# MINI_SAM_D51_r002_b002.net
KiCad netlist of a schematic drawn in EAGLE
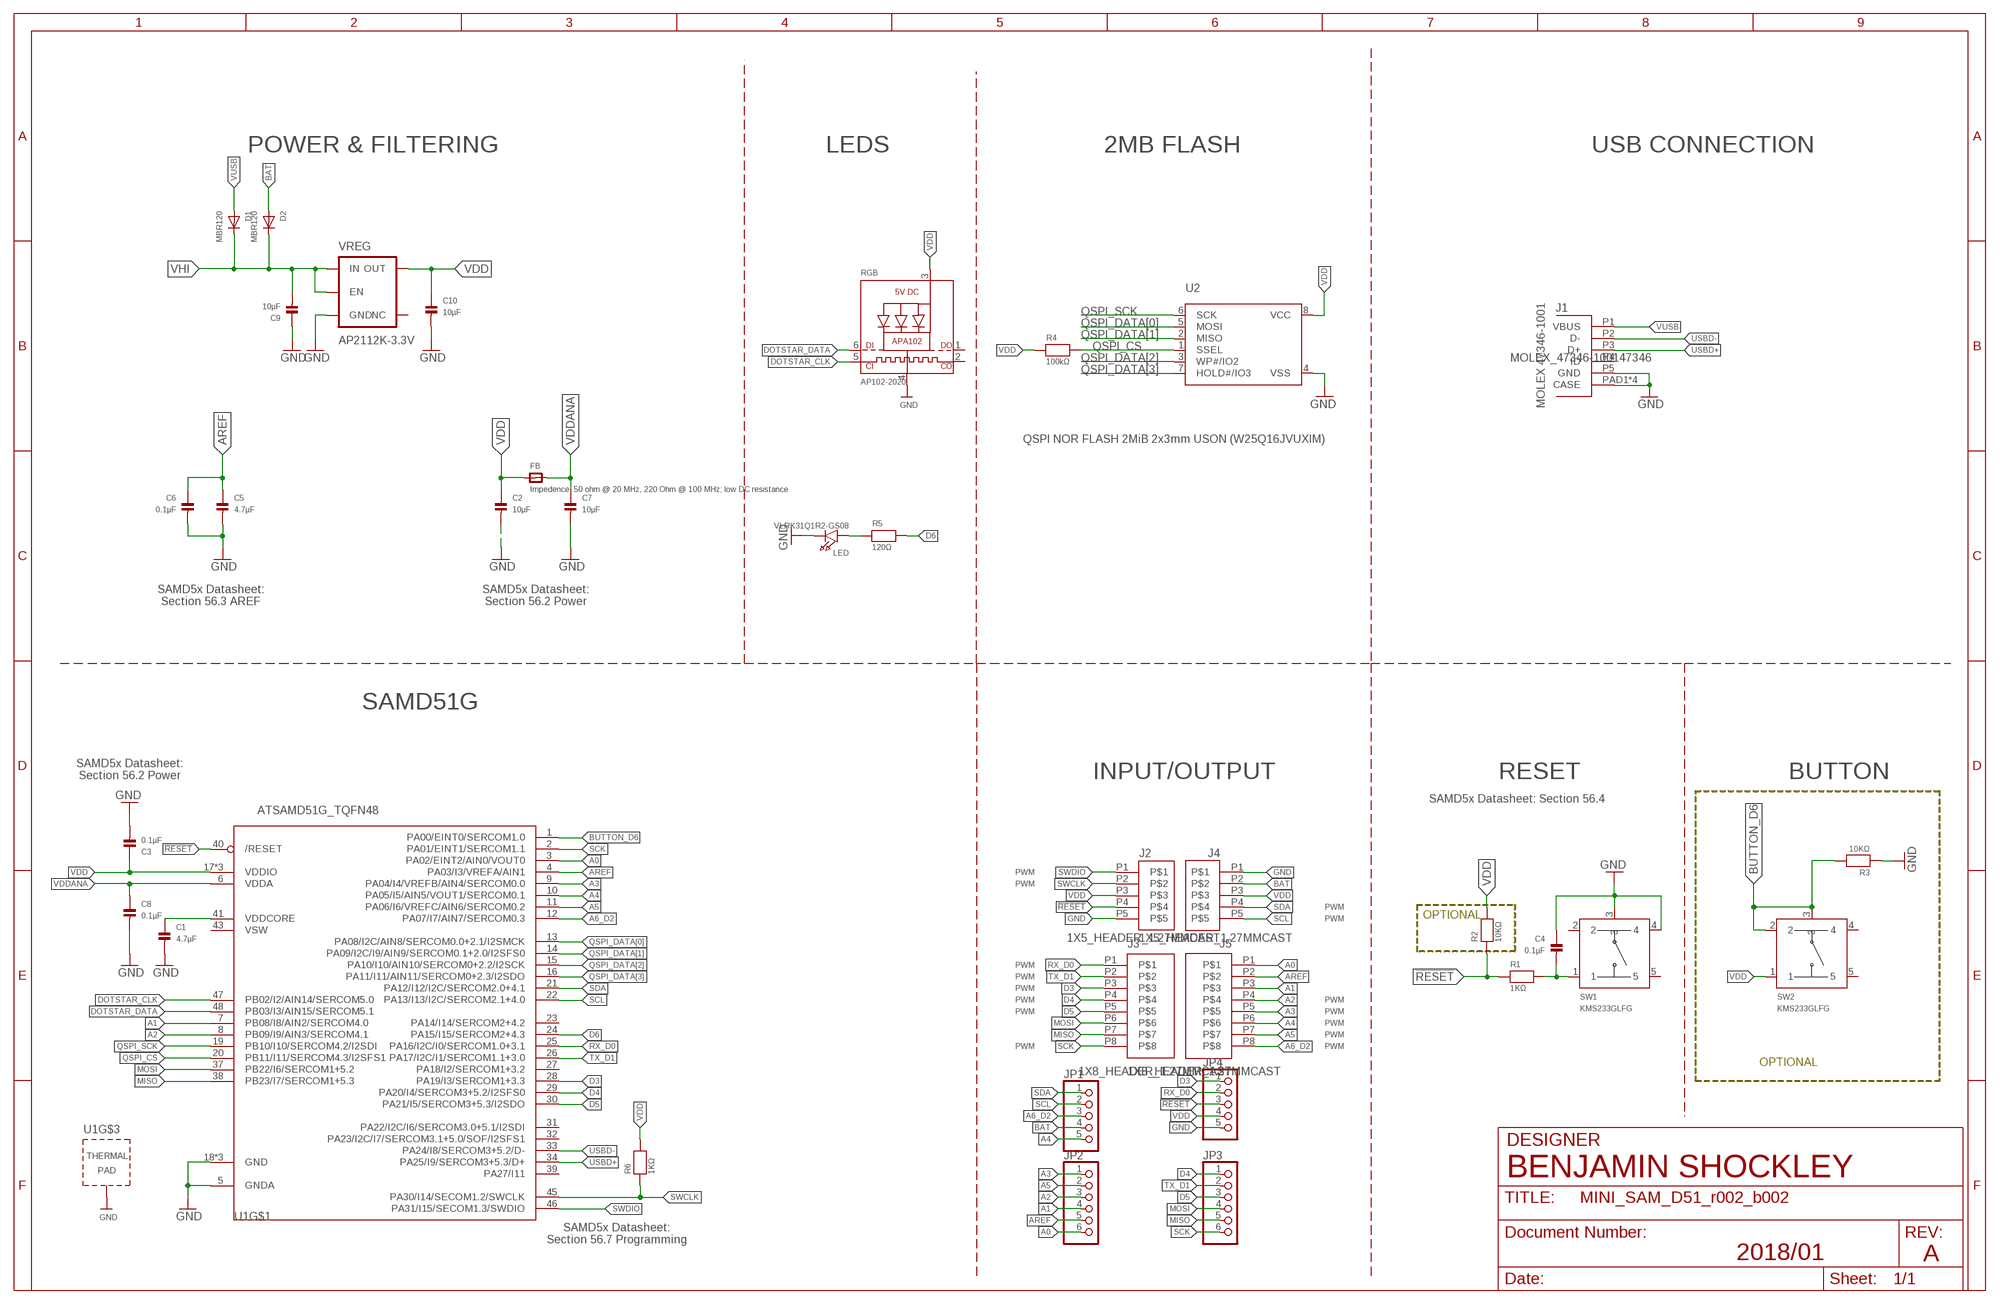
[diagram p0: schematic, sheet 1]

(export (version "E")
  (design (tool "Eeschema 10.0.6"))
  (components
    (comp (ref "C1")
      (value "4.7µF")
      (footprint "eagle-import:_0603MP")
      (libsource (lib "eagle-import") (part "CAP_CERAMIC_0603MP"))
    )
    (comp (ref "C2")
      (value "10µF")
      (footprint "eagle-import:_0603MP")
      (libsource (lib "eagle-import") (part "CAP_CERAMIC_0603MP"))
    )
    (comp (ref "C3")
      (value "0.1µF")
      (footprint "eagle-import:_0603MP")
      (libsource (lib "eagle-import") (part "CAP_CERAMIC_0603MP"))
    )
    (comp (ref "C4")
      (value "0.1µF")
      (footprint "eagle-import:_0603MP")
      (libsource (lib "eagle-import") (part "CAP_CERAMIC_0603MP"))
    )
    (comp (ref "C5")
      (value "4.7µF")
      (footprint "eagle-import:_0603MP")
      (libsource (lib "eagle-import") (part "CAP_CERAMIC_0603MP"))
    )
    (comp (ref "C6")
      (value "0.1µF")
      (footprint "eagle-import:_0603MP")
      (libsource (lib "eagle-import") (part "CAP_CERAMIC_0603MP"))
    )
    (comp (ref "C7")
      (value "10µF")
      (footprint "eagle-import:_0603MP")
      (libsource (lib "eagle-import") (part "CAP_CERAMIC_0603MP"))
    )
    (comp (ref "C8")
      (value "0.1µF")
      (footprint "eagle-import:_0603MP")
      (libsource (lib "eagle-import") (part "CAP_CERAMIC_0603MP"))
    )
    (comp (ref "C9")
      (value "10µF")
      (footprint "eagle-import:_0603MP")
      (libsource (lib "eagle-import") (part "CAP_CERAMIC_0603MP"))
    )
    (comp (ref "C10")
      (value "10µF")
      (footprint "eagle-import:_0603MP")
      (libsource (lib "eagle-import") (part "CAP_CERAMIC_0603MP"))
    )
    (comp (ref "D1")
      (value "MBR120")
      (footprint "eagle-import:SOD-123FL")
      (libsource (lib "eagle-import") (part "DIODE_SOD-123FL"))
    )
    (comp (ref "D2")
      (value "MBR120")
      (footprint "eagle-import:SOD-123FL")
      (libsource (lib "eagle-import") (part "DIODE_SOD-123FL"))
    )
    (comp (ref "FB")
      (value "Impedence: 50 ohm @ 20 MHz, 220 Ohm @ 100 MHz; low DC resistance")
      (footprint "eagle-import:_0603MP")
      (libsource (lib "eagle-import") (part "FERRITE_0603MP"))
    )
    (comp (ref "J1")
      (value "MOLEX_47346-100147346")
      (footprint "eagle-import:MOLEX_47346-1001")
      (libsource (lib "eagle-import") (part "MOLEX_47346-100147346"))
    )
    (comp (ref "J2")
      (value "1X5_HEADER_1.27MMCAST")
      (footprint "eagle-import:1X5_HEADER_1.27MM_CASTELLATED")
      (libsource (lib "eagle-import") (part "1X5_HEADER_1.27MMCAST"))
    )
    (comp (ref "J3")
      (value "1X8_HEADER_1.27MMCAST")
      (footprint "eagle-import:1X8_HEADER_1.27MM_CASTELLATED")
      (libsource (lib "eagle-import") (part "1X8_HEADER_1.27MMCAST"))
    )
    (comp (ref "J4")
      (value "1X5_HEADER_1.27MMCAST")
      (footprint "eagle-import:1X5_HEADER_1.27MM_CASTELLATED")
      (libsource (lib "eagle-import") (part "1X5_HEADER_1.27MMCAST"))
    )
    (comp (ref "J5")
      (value "1X8_HEADER_1.27MMCAST")
      (footprint "eagle-import:1X8_HEADER_1.27MM_CASTELLATED")
      (libsource (lib "eagle-import") (part "1X8_HEADER_1.27MMCAST"))
    )
    (comp (ref "JP1")
      (value "PINHD-1X51X05_SMT")
      (footprint "eagle-import:1X05_SMT")
      (libsource (lib "eagle-import") (part "PINHD-1X51X05_SMT"))
    )
    (comp (ref "JP2")
      (value "PINHD-1X61X06_SMT")
      (footprint "eagle-import:1X06_SMT")
      (libsource (lib "eagle-import") (part "PINHD-1X61X06_SMT"))
    )
    (comp (ref "JP3")
      (value "PINHD-1X6REV")
      (footprint "eagle-import:1X06_SMT_REV")
      (libsource (lib "eagle-import") (part "PINHD-1X6REV"))
    )
    (comp (ref "JP4")
      (value "PINHD-1X51X05_SMT")
      (footprint "eagle-import:1X05_SMT")
      (libsource (lib "eagle-import") (part "PINHD-1X51X05_SMT"))
    )
    (comp (ref "LED")
      (value "VLRK31Q1R2-GS08")
      (footprint "eagle-import:REVERSE_MOUNT_LED")
      (libsource (lib "eagle-import") (part "REVERSEMOUNTLED"))
    )
    (comp (ref "R1")
      (value "1KΩ")
      (footprint "eagle-import:_0603MP")
      (libsource (lib "eagle-import") (part "RESISTOR_0603MP"))
    )
    (comp (ref "R2")
      (value "10KΩ")
      (footprint "eagle-import:_0603MP")
      (libsource (lib "eagle-import") (part "RESISTOR_0603MP"))
    )
    (comp (ref "R3")
      (value "10KΩ")
      (footprint "eagle-import:_0603MP")
      (libsource (lib "eagle-import") (part "RESISTOR_0603MP"))
    )
    (comp (ref "R4")
      (value "100kΩ")
      (footprint "eagle-import:_0603MP")
      (libsource (lib "eagle-import") (part "RESISTOR_0603MP"))
    )
    (comp (ref "R5")
      (value "120Ω")
      (footprint "eagle-import:_0603MP")
      (libsource (lib "eagle-import") (part "RESISTOR_0603MP"))
    )
    (comp (ref "R6")
      (value "1KΩ")
      (footprint "eagle-import:_0603MP")
      (libsource (lib "eagle-import") (part "RESISTOR_0603MP"))
    )
    (comp (ref "RGB")
      (value "AP102-2020")
      (footprint "eagle-import:APA102_2020")
      (libsource (lib "eagle-import") (part "APA1022020"))
    )
    (comp (ref "SW1")
      (value "KMS233GLFG")
      (footprint "eagle-import:KMS_SWITCH")
      (libsource (lib "eagle-import") (part "KMS_SWITCHKMS"))
    )
    (comp (ref "SW2")
      (value "KMS233GLFG")
      (footprint "eagle-import:KMS_SWITCH")
      (libsource (lib "eagle-import") (part "KMS_SWITCHKMS"))
    )
    (comp (ref "U1")
      (value "ATSAMD51G_TQFN48")
      (footprint "eagle-import:TQFN48_7MM")
      (libsource (lib "eagle-import") (part "ATSAMD51G_TQFN48"))
    )
    (comp (ref "U2")
      (value "QSPI NOR FLASH 2MiB 2x3mm USON (W25Q16JVUXIM)")
      (footprint "eagle-import:USON8")
      (libsource (lib "eagle-import") (part "SPIFLASH_8PINUX"))
    )
    (comp (ref "VREG")
      (value "AP2112K-3.3V")
      (footprint "eagle-import:SOT23-5")
      (libsource (lib "eagle-import") (part "V_REG_AP2112K-3.3V"))
    )
  )
  (nets
    (net (code "1") (name "/VSW") (class "Default")
      (node (ref "U1") (pin "43") (pinfunction "VSW_43") (pintype "power_in"))
    )
    (net (code "2") (name "/~{RESET}") (class "Default")
      (node (ref "J2") (pin "P4") (pinfunction "P$4_P4") (pintype "bidirectional"))
      (node (ref "JP4") (pin "3") (pinfunction "3_3") (pintype "passive"))
      (node (ref "R1") (pin "1") (pinfunction "1_1") (pintype "passive"))
      (node (ref "R2") (pin "1") (pinfunction "1_1") (pintype "passive"))
      (node (ref "U1") (pin "40") (pinfunction "/RESET_40") (pintype "bidirectional"))
    )
    (net (code "3") (name "A0") (class "Default")
      (node (ref "J5") (pin "P1") (pinfunction "P$1_P1") (pintype "bidirectional"))
      (node (ref "JP2") (pin "6") (pinfunction "6_6") (pintype "passive"))
      (node (ref "U1") (pin "3") (pinfunction "PA02/EINT2/AIN0/VOUT0_3") (pintype "bidirectional"))
    )
    (net (code "4") (name "A1") (class "Default")
      (node (ref "J5") (pin "P3") (pinfunction "P$3_P3") (pintype "bidirectional"))
      (node (ref "JP2") (pin "4") (pinfunction "4_4") (pintype "passive"))
      (node (ref "U1") (pin "7") (pinfunction "PB08/I8/AIN2/SERCOM4.0_7") (pintype "bidirectional"))
    )
    (net (code "5") (name "A2") (class "Default")
      (node (ref "J5") (pin "P4") (pinfunction "P$4_P4") (pintype "bidirectional"))
      (node (ref "JP2") (pin "3") (pinfunction "3_3") (pintype "passive"))
      (node (ref "U1") (pin "8") (pinfunction "PB09/I9/AIN3/SERCOM4.1_8") (pintype "bidirectional"))
    )
    (net (code "6") (name "A3") (class "Default")
      (node (ref "J5") (pin "P5") (pinfunction "P$5_P5") (pintype "bidirectional"))
      (node (ref "JP2") (pin "1") (pinfunction "1_1") (pintype "passive"))
      (node (ref "U1") (pin "9") (pinfunction "PA04/I4/VREFB/AIN4/SERCOM0.0_9") (pintype "bidirectional"))
    )
    (net (code "7") (name "A4") (class "Default")
      (node (ref "J5") (pin "P6") (pinfunction "P$6_P6") (pintype "bidirectional"))
      (node (ref "JP1") (pin "5") (pinfunction "5_5") (pintype "passive"))
      (node (ref "U1") (pin "10") (pinfunction "PA05/I5/AIN5/VOUT1/SERCOM0.1_10") (pintype "bidirectional"))
    )
    (net (code "8") (name "A5") (class "Default")
      (node (ref "J5") (pin "P7") (pinfunction "P$7_P7") (pintype "bidirectional"))
      (node (ref "JP2") (pin "2") (pinfunction "2_2") (pintype "passive"))
      (node (ref "U1") (pin "11") (pinfunction "PA06/I6/VREFC/AIN6/SERCOM0.2_11") (pintype "bidirectional"))
    )
    (net (code "9") (name "A6_D2") (class "Default")
      (node (ref "J5") (pin "P8") (pinfunction "P$8_P8") (pintype "bidirectional"))
      (node (ref "JP1") (pin "3") (pinfunction "3_3") (pintype "passive"))
      (node (ref "U1") (pin "12") (pinfunction "PA07/I7/AIN7/SERCOM0.3_12") (pintype "bidirectional"))
    )
    (net (code "10") (name "AREF") (class "Default")
      (node (ref "C5") (pin "1") (pinfunction "P$1_1") (pintype "passive"))
      (node (ref "C6") (pin "1") (pinfunction "P$1_1") (pintype "passive"))
      (node (ref "J5") (pin "P2") (pinfunction "P$2_P2") (pintype "bidirectional"))
      (node (ref "JP2") (pin "5") (pinfunction "5_5") (pintype "passive"))
      (node (ref "U1") (pin "4") (pinfunction "PA03/I3/VREFA/AIN1_4") (pintype "bidirectional"))
    )
    (net (code "11") (name "BAT") (class "Default")
      (node (ref "D2") (pin "A") (pinfunction "A_A") (pintype "passive"))
      (node (ref "J4") (pin "P2") (pinfunction "P$2_P2") (pintype "bidirectional"))
      (node (ref "JP1") (pin "4") (pinfunction "4_4") (pintype "passive"))
    )
    (net (code "12") (name "BUTTON_D6") (class "Default")
      (node (ref "R3") (pin "2") (pinfunction "2_2") (pintype "passive"))
      (node (ref "SW2") (pin "2") (pinfunction "2_2") (pintype "bidirectional"))
      (node (ref "SW2") (pin "3") (pinfunction "3_3") (pintype "bidirectional"))
      (node (ref "U1") (pin "1") (pinfunction "PA00/EINT0/SERCOM1.0_1") (pintype "bidirectional"))
    )
    (net (code "13") (name "D3") (class "Default")
      (node (ref "J3") (pin "P3") (pinfunction "P$3_P3") (pintype "bidirectional"))
      (node (ref "JP4") (pin "1") (pinfunction "1_1") (pintype "passive"))
      (node (ref "U1") (pin "28") (pinfunction "PA19/I3/SERCOM1+3.3_28") (pintype "bidirectional"))
    )
    (net (code "14") (name "D4") (class "Default")
      (node (ref "J3") (pin "P4") (pinfunction "P$4_P4") (pintype "bidirectional"))
      (node (ref "JP3") (pin "1") (pinfunction "1_1") (pintype "passive"))
      (node (ref "U1") (pin "29") (pinfunction "PA20/I4/SERCOM3+5.2/I2SFS0_29") (pintype "bidirectional"))
    )
    (net (code "15") (name "D5") (class "Default")
      (node (ref "J3") (pin "P5") (pinfunction "P$5_P5") (pintype "bidirectional"))
      (node (ref "JP3") (pin "3") (pinfunction "3_3") (pintype "passive"))
      (node (ref "U1") (pin "30") (pinfunction "PA21/I5/SERCOM3+5.3/I2SDO_30") (pintype "bidirectional"))
    )
    (net (code "16") (name "D6") (class "Default")
      (node (ref "R5") (pin "2") (pinfunction "2_2") (pintype "passive"))
      (node (ref "U1") (pin "24") (pinfunction "PA15/I15/SERCOM2+4.3_24") (pintype "bidirectional"))
    )
    (net (code "17") (name "DOTSTAR_CLK") (class "Default")
      (node (ref "RGB") (pin "5") (pinfunction "CKI_5") (pintype "input"))
      (node (ref "U1") (pin "47") (pinfunction "PB02/I2/AIN14/SERCOM5.0_47") (pintype "bidirectional"))
    )
    (net (code "18") (name "DOTSTAR_DATA") (class "Default")
      (node (ref "RGB") (pin "6") (pinfunction "DI_6") (pintype "input"))
      (node (ref "U1") (pin "48") (pinfunction "PB03/I3/AIN15/SERCOM5.1_48") (pintype "bidirectional"))
    )
    (net (code "19") (name "GND") (class "Default")
      (node (ref "C1") (pin "2") (pinfunction "P$2_2") (pintype "passive"))
      (node (ref "C10") (pin "2") (pinfunction "P$2_2") (pintype "passive"))
      (node (ref "C2") (pin "2") (pinfunction "P$2_2") (pintype "passive"))
      (node (ref "C3") (pin "2") (pinfunction "P$2_2") (pintype "passive"))
      (node (ref "C4") (pin "1") (pinfunction "P$1_1") (pintype "passive"))
      (node (ref "C5") (pin "2") (pinfunction "P$2_2") (pintype "passive"))
      (node (ref "C6") (pin "2") (pinfunction "P$2_2") (pintype "passive"))
      (node (ref "C7") (pin "2") (pinfunction "P$2_2") (pintype "passive"))
      (node (ref "C8") (pin "2") (pinfunction "P$2_2") (pintype "passive"))
      (node (ref "C9") (pin "1") (pinfunction "P$1_1") (pintype "passive"))
      (node (ref "J1") (pin "P5") (pinfunction "GND_P5") (pintype "power_in"))
      (node (ref "J1") (pin "PAD1") (pinfunction "CASE_PAD1") (pintype "bidirectional"))
      (node (ref "J1") (pin "PAD2") (pinfunction "CASE_PAD2") (pintype "bidirectional"))
      (node (ref "J1") (pin "PAD3") (pinfunction "CASE_PAD3") (pintype "bidirectional"))
      (node (ref "J1") (pin "PAD4") (pinfunction "CASE_PAD4") (pintype "bidirectional"))
      (node (ref "J2") (pin "P5") (pinfunction "P$5_P5") (pintype "bidirectional"))
      (node (ref "J4") (pin "P1") (pinfunction "P$1_P1") (pintype "bidirectional"))
      (node (ref "JP4") (pin "5") (pinfunction "5_5") (pintype "passive"))
      (node (ref "LED") (pin "C") (pinfunction "C_C") (pintype "passive"))
      (node (ref "R3") (pin "1") (pinfunction "1_1") (pintype "passive"))
      (node (ref "RGB") (pin "4") (pinfunction "GND_4") (pintype "power_in"))
      (node (ref "SW1") (pin "3") (pinfunction "3_3") (pintype "bidirectional"))
      (node (ref "SW1") (pin "4") (pinfunction "4_4") (pintype "bidirectional"))
      (node (ref "U1") (pin "18") (pinfunction "GND_18") (pintype "power_in"))
      (node (ref "U1") (pin "35") (pinfunction "GND_35") (pintype "power_in"))
      (node (ref "U1") (pin "42") (pinfunction "GND_42") (pintype "power_in"))
      (node (ref "U1") (pin "5") (pinfunction "GNDA_5") (pintype "power_in"))
      (node (ref "U1") (pin "THERMAL") (pinfunction "TP_THERMAL") (pintype "power_in"))
      (node (ref "U2") (pin "4") (pinfunction "VSS_4") (pintype "bidirectional"))
      (node (ref "VREG") (pin "2") (pinfunction "GND_2") (pintype "input"))
    )
    (net (code "20") (name "MISO") (class "Default")
      (node (ref "J3") (pin "P7") (pinfunction "P$7_P7") (pintype "bidirectional"))
      (node (ref "JP3") (pin "5") (pinfunction "5_5") (pintype "passive"))
      (node (ref "U1") (pin "38") (pinfunction "PB23/I7/SERCOM1+5.3_38") (pintype "bidirectional"))
    )
    (net (code "21") (name "MOSI") (class "Default")
      (node (ref "J3") (pin "P6") (pinfunction "P$6_P6") (pintype "bidirectional"))
      (node (ref "JP3") (pin "4") (pinfunction "4_4") (pintype "passive"))
      (node (ref "U1") (pin "37") (pinfunction "PB22/I6/SERCOM1+5.2_37") (pintype "bidirectional"))
    )
    (net (code "22") (name "Net-(C1-P$1)") (class "Default")
      (node (ref "C1") (pin "1") (pinfunction "P$1_1") (pintype "passive"))
      (node (ref "U1") (pin "41") (pinfunction "VDDCORE_41") (pintype "power_in"))
    )
    (net (code "23") (name "Net-(C4-P$2)") (class "Default")
      (node (ref "C4") (pin "2") (pinfunction "P$2_2") (pintype "passive"))
      (node (ref "R1") (pin "2") (pinfunction "2_2") (pintype "passive"))
      (node (ref "SW1") (pin "1") (pinfunction "1_1") (pintype "bidirectional"))
    )
    (net (code "24") (name "Net-(LED-PadA)") (class "Default")
      (node (ref "LED") (pin "A") (pinfunction "A_A") (pintype "passive"))
      (node (ref "R5") (pin "1") (pinfunction "1_1") (pintype "passive"))
    )
    (net (code "25") (name "QSPI_CS") (class "Default")
      (node (ref "R4") (pin "2") (pinfunction "2_2") (pintype "passive"))
      (node (ref "U1") (pin "20") (pinfunction "PB11/I11/SERCOM4.3/I2SFS1_20") (pintype "bidirectional"))
      (node (ref "U2") (pin "1") (pinfunction "SSEL_1") (pintype "bidirectional"))
    )
    (net (code "26") (name "QSPI_DATA[0]") (class "Default")
      (node (ref "U1") (pin "13") (pinfunction "PA08/I2C/AIN8/SERCOM0.0+2.1/I2SMCK_13") (pintype "bidirectional"))
      (node (ref "U2") (pin "5") (pinfunction "MOSI_5") (pintype "bidirectional"))
    )
    (net (code "27") (name "QSPI_DATA[1]") (class "Default")
      (node (ref "U1") (pin "14") (pinfunction "PA09/I2C/I9/AIN9/SERCOM0.1+2.0/I2SFS0_14") (pintype "bidirectional"))
      (node (ref "U2") (pin "2") (pinfunction "MISO_2") (pintype "bidirectional"))
    )
    (net (code "28") (name "QSPI_DATA[2]") (class "Default")
      (node (ref "U1") (pin "15") (pinfunction "PA10/I10/AIN10/SERCOM0+2.2/I2SCK_15") (pintype "bidirectional"))
      (node (ref "U2") (pin "3") (pinfunction "WP#/IO2_3") (pintype "bidirectional"))
    )
    (net (code "29") (name "QSPI_DATA[3]") (class "Default")
      (node (ref "U1") (pin "16") (pinfunction "PA11/I11/AIN11/SERCOM0+2.3/I2SDO_16") (pintype "bidirectional"))
      (node (ref "U2") (pin "7") (pinfunction "HOLD#/IO3_7") (pintype "bidirectional"))
    )
    (net (code "30") (name "QSPI_SCK") (class "Default")
      (node (ref "U1") (pin "19") (pinfunction "PB10/I10/SERCOM4.2/I2SDI_19") (pintype "bidirectional"))
      (node (ref "U2") (pin "6") (pinfunction "SCK_6") (pintype "bidirectional"))
    )
    (net (code "31") (name "RX_D0") (class "Default")
      (node (ref "J3") (pin "P1") (pinfunction "P$1_P1") (pintype "bidirectional"))
      (node (ref "JP4") (pin "2") (pinfunction "2_2") (pintype "passive"))
      (node (ref "U1") (pin "25") (pinfunction "PA16/I2C/I0/SERCOM1.0+3.1_25") (pintype "bidirectional"))
    )
    (net (code "32") (name "SCK") (class "Default")
      (node (ref "J3") (pin "P8") (pinfunction "P$8_P8") (pintype "bidirectional"))
      (node (ref "JP3") (pin "6") (pinfunction "6_6") (pintype "passive"))
      (node (ref "U1") (pin "2") (pinfunction "PA01/EINT1/SERCOM1.1_2") (pintype "bidirectional"))
    )
    (net (code "33") (name "SCL") (class "Default")
      (node (ref "J4") (pin "P5") (pinfunction "P$5_P5") (pintype "bidirectional"))
      (node (ref "JP1") (pin "2") (pinfunction "2_2") (pintype "passive"))
      (node (ref "U1") (pin "22") (pinfunction "PA13/I13/I2C/SERCOM2.1+4.0_22") (pintype "bidirectional"))
    )
    (net (code "34") (name "SDA") (class "Default")
      (node (ref "J4") (pin "P4") (pinfunction "P$4_P4") (pintype "bidirectional"))
      (node (ref "JP1") (pin "1") (pinfunction "1_1") (pintype "passive"))
      (node (ref "U1") (pin "21") (pinfunction "PA12/I12/I2C/SERCOM2.0+4.1_21") (pintype "bidirectional"))
    )
    (net (code "35") (name "SWCLK") (class "Default")
      (node (ref "J2") (pin "P2") (pinfunction "P$2_P2") (pintype "bidirectional"))
      (node (ref "R6") (pin "1") (pinfunction "1_1") (pintype "passive"))
      (node (ref "U1") (pin "45") (pinfunction "PA30/I14/SECOM1.2/SWCLK_45") (pintype "bidirectional"))
    )
    (net (code "36") (name "SWDIO") (class "Default")
      (node (ref "J2") (pin "P1") (pinfunction "P$1_P1") (pintype "bidirectional"))
      (node (ref "U1") (pin "46") (pinfunction "PA31/I15/SECOM1.3/SWDIO_46") (pintype "bidirectional"))
    )
    (net (code "37") (name "TX_D1") (class "Default")
      (node (ref "J3") (pin "P2") (pinfunction "P$2_P2") (pintype "bidirectional"))
      (node (ref "JP3") (pin "2") (pinfunction "2_2") (pintype "passive"))
      (node (ref "U1") (pin "26") (pinfunction "PA17/I2C/I1/SERCOM1.1+3.0_26") (pintype "bidirectional"))
    )
    (net (code "38") (name "USBD+") (class "Default")
      (node (ref "J1") (pin "P3") (pinfunction "D+_P3") (pintype "bidirectional"))
      (node (ref "U1") (pin "34") (pinfunction "PA25/I9/SERCOM3+5.3/D+_34") (pintype "bidirectional"))
    )
    (net (code "39") (name "USBD-") (class "Default")
      (node (ref "J1") (pin "P2") (pinfunction "D-_P2") (pintype "bidirectional"))
      (node (ref "U1") (pin "33") (pinfunction "PA24/I8/SERCOM3+5.2/D-_33") (pintype "bidirectional"))
    )
    (net (code "40") (name "VDD") (class "Default")
      (node (ref "C10") (pin "1") (pinfunction "P$1_1") (pintype "passive"))
      (node (ref "C2") (pin "1") (pinfunction "P$1_1") (pintype "passive"))
      (node (ref "C3") (pin "1") (pinfunction "P$1_1") (pintype "passive"))
      (node (ref "FB") (pin "1") (pinfunction "P$1_1") (pintype "passive"))
      (node (ref "J2") (pin "P3") (pinfunction "P$3_P3") (pintype "bidirectional"))
      (node (ref "J4") (pin "P3") (pinfunction "P$3_P3") (pintype "bidirectional"))
      (node (ref "JP4") (pin "4") (pinfunction "4_4") (pintype "passive"))
      (node (ref "R2") (pin "2") (pinfunction "2_2") (pintype "passive"))
      (node (ref "R4") (pin "1") (pinfunction "1_1") (pintype "passive"))
      (node (ref "R6") (pin "2") (pinfunction "2_2") (pintype "passive"))
      (node (ref "RGB") (pin "3") (pinfunction "VDD_3") (pintype "power_in"))
      (node (ref "SW2") (pin "1") (pinfunction "1_1") (pintype "bidirectional"))
      (node (ref "U1") (pin "17") (pinfunction "VDDIO_17") (pintype "power_in"))
      (node (ref "U1") (pin "36") (pinfunction "VDDIO_36") (pintype "power_in"))
      (node (ref "U1") (pin "44") (pinfunction "VDDIO_44") (pintype "power_in"))
      (node (ref "U2") (pin "8") (pinfunction "VCC_8") (pintype "bidirectional"))
      (node (ref "VREG") (pin "5") (pinfunction "OUT_5") (pintype "passive"))
    )
    (net (code "41") (name "VDDANA") (class "Default")
      (node (ref "C7") (pin "1") (pinfunction "P$1_1") (pintype "passive"))
      (node (ref "C8") (pin "1") (pinfunction "P$1_1") (pintype "passive"))
      (node (ref "FB") (pin "2") (pinfunction "P$2_2") (pintype "passive"))
      (node (ref "U1") (pin "6") (pinfunction "VDDA_6") (pintype "power_in"))
    )
    (net (code "42") (name "VHI") (class "Default")
      (node (ref "C9") (pin "2") (pinfunction "P$2_2") (pintype "passive"))
      (node (ref "D1") (pin "C") (pinfunction "C_C") (pintype "passive"))
      (node (ref "D2") (pin "C") (pinfunction "C_C") (pintype "passive"))
      (node (ref "VREG") (pin "1") (pinfunction "IN_1") (pintype "input"))
      (node (ref "VREG") (pin "3") (pinfunction "EN_3") (pintype "input"))
    )
    (net (code "43") (name "VUSB") (class "Default")
      (node (ref "D1") (pin "A") (pinfunction "A_A") (pintype "passive"))
      (node (ref "J1") (pin "P1") (pinfunction "VBUS_P1") (pintype "power_in"))
    )
    (net (code "44") (name "unconnected-(J1-ID-PadP4)") (class "Default")
      (node (ref "J1") (pin "P4") (pinfunction "ID_P4") (pintype "bidirectional"))
    )
    (net (code "45") (name "unconnected-(RGB-CKO-Pad2)") (class "Default")
      (node (ref "RGB") (pin "2") (pinfunction "CKO_2") (pintype "output"))
    )
    (net (code "46") (name "unconnected-(RGB-DO-Pad1)") (class "Default")
      (node (ref "RGB") (pin "1") (pinfunction "DO_1") (pintype "output"))
    )
    (net (code "47") (name "unconnected-(SW1-Pad2)") (class "Default")
      (node (ref "SW1") (pin "2") (pinfunction "2_2") (pintype "bidirectional"))
    )
    (net (code "48") (name "unconnected-(SW1-Pad5)") (class "Default")
      (node (ref "SW1") (pin "5") (pinfunction "5_5") (pintype "bidirectional"))
    )
    (net (code "49") (name "unconnected-(SW2-Pad4)") (class "Default")
      (node (ref "SW2") (pin "4") (pinfunction "4_4") (pintype "bidirectional"))
    )
    (net (code "50") (name "unconnected-(SW2-Pad5)") (class "Default")
      (node (ref "SW2") (pin "5") (pinfunction "5_5") (pintype "bidirectional"))
    )
    (net (code "51") (name "unconnected-(U1A-PA14{slash}I14{slash}SERCOM2+4.2-Pad23)") (class "Default")
      (node (ref "U1") (pin "23") (pinfunction "PA14/I14/SERCOM2+4.2_23") (pintype "bidirectional"))
    )
    (net (code "52") (name "unconnected-(U1A-PA18{slash}I2{slash}SERCOM1+3.2-Pad27)") (class "Default")
      (node (ref "U1") (pin "27") (pinfunction "PA18/I2/SERCOM1+3.2_27") (pintype "bidirectional"))
    )
    (net (code "53") (name "unconnected-(U1A-PA22{slash}I2C{slash}I6{slash}SERCOM3.0+5.1{slash}I2SDI-Pad31)") (class "Default")
      (node (ref "U1") (pin "31") (pinfunction "PA22/I2C/I6/SERCOM3.0+5.1/I2SDI_31") (pintype "bidirectional"))
    )
    (net (code "54") (name "unconnected-(U1A-PA23{slash}I2C{slash}I7{slash}SERCOM3.1+5.0{slash}SOF{slash}I2SFS1-Pad32)") (class "Default")
      (node (ref "U1") (pin "32") (pinfunction "PA23/I2C/I7/SERCOM3.1+5.0/SOF/I2SFS1_32") (pintype "bidirectional"))
    )
    (net (code "55") (name "unconnected-(U1A-PA27{slash}I11-Pad39)") (class "Default")
      (node (ref "U1") (pin "39") (pinfunction "PA27/I11_39") (pintype "bidirectional"))
    )
    (net (code "56") (name "unconnected-(VREG-NC-Pad4)") (class "Default")
      (node (ref "VREG") (pin "4") (pinfunction "NC_4") (pintype "input"))
    )
  )
)
